# Main_Board.net
KiCad netlist of a schematic drawn in EAGLE
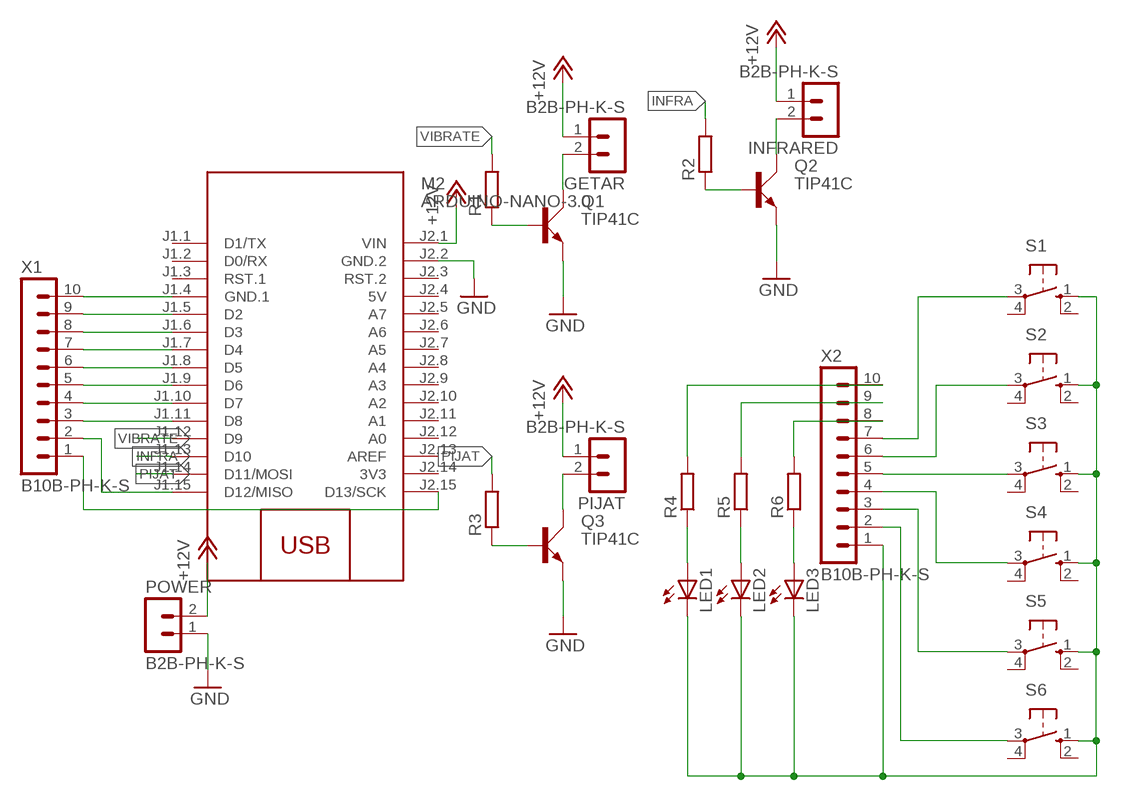
[diagram p0: schematic, sheet 1]

(export (version "E")
  (design (tool "Eeschema 10.0.6"))
  (components
    (comp (ref "GETAR")
      (value "B2B-PH-K-S")
      (footprint "eagle-import:B2B-PH-K-S")
      (libsource (lib "eagle-import") (part "B2B-PH-K-S"))
    )
    (comp (ref "INFRARED")
      (value "B2B-PH-K-S")
      (footprint "eagle-import:B2B-PH-K-S")
      (libsource (lib "eagle-import") (part "B2B-PH-K-S"))
    )
    (comp (ref "LED1")
      (value "LED5MM")
      (footprint "eagle-import:LED5MM")
      (libsource (lib "eagle-import") (part "LED5MM"))
    )
    (comp (ref "LED2")
      (value "LED5MM")
      (footprint "eagle-import:LED5MM")
      (libsource (lib "eagle-import") (part "LED5MM"))
    )
    (comp (ref "LED3")
      (value "LED5MM")
      (footprint "eagle-import:LED5MM")
      (libsource (lib "eagle-import") (part "LED5MM"))
    )
    (comp (ref "M2")
      (value "ARDUINO-NANO-3.0")
      (footprint "eagle-import:ARDUINO-NANO-3.0")
      (libsource (lib "eagle-import") (part "ARDUINO-NANO-3.0"))
    )
    (comp (ref "PIJAT")
      (value "B2B-PH-K-S")
      (footprint "eagle-import:B2B-PH-K-S")
      (libsource (lib "eagle-import") (part "B2B-PH-K-S"))
    )
    (comp (ref "POWER")
      (value "B2B-PH-K-S")
      (footprint "eagle-import:B2B-PH-K-S")
      (libsource (lib "eagle-import") (part "B2B-PH-K-S"))
    )
    (comp (ref "Q1")
      (value "TIP41C")
      (footprint "eagle-import:TO220AV")
      (libsource (lib "eagle-import") (part "TIP41C"))
    )
    (comp (ref "Q2")
      (value "TIP41C")
      (footprint "eagle-import:TO220AV")
      (libsource (lib "eagle-import") (part "TIP41C"))
    )
    (comp (ref "Q3")
      (value "TIP41C")
      (footprint "eagle-import:TO220AV")
      (libsource (lib "eagle-import") (part "TIP41C"))
    )
    (comp (ref "R1")
      (value "R-EU_0207/12")
      (footprint "eagle-import:0207_12")
      (libsource (lib "eagle-import") (part "R-EU_0207/12"))
    )
    (comp (ref "R2")
      (value "R-EU_0207/12")
      (footprint "eagle-import:0207_12")
      (libsource (lib "eagle-import") (part "R-EU_0207/12"))
    )
    (comp (ref "R3")
      (value "R-EU_0207/12")
      (footprint "eagle-import:0207_12")
      (libsource (lib "eagle-import") (part "R-EU_0207/12"))
    )
    (comp (ref "R4")
      (value "R-EU_0207/12")
      (footprint "eagle-import:0207_12")
      (libsource (lib "eagle-import") (part "R-EU_0207/12"))
    )
    (comp (ref "R5")
      (value "R-EU_0207/12")
      (footprint "eagle-import:0207_12")
      (libsource (lib "eagle-import") (part "R-EU_0207/12"))
    )
    (comp (ref "R6")
      (value "R-EU_0207/12")
      (footprint "eagle-import:0207_12")
      (libsource (lib "eagle-import") (part "R-EU_0207/12"))
    )
    (comp (ref "S1")
      (value "40-XX")
      (footprint "eagle-import:B3F-40XX")
      (fields (field (name "MF") "OMRON COMPONENTS USA") (field (name "MPN") "B3F-4000"))
      (libsource (lib "eagle-import") (part "40-XX"))
    )
    (comp (ref "S2")
      (value "40-XX")
      (footprint "eagle-import:B3F-40XX")
      (fields (field (name "MF") "OMRON COMPONENTS USA") (field (name "MPN") "B3F-4000"))
      (libsource (lib "eagle-import") (part "40-XX"))
    )
    (comp (ref "S3")
      (value "40-XX")
      (footprint "eagle-import:B3F-40XX")
      (fields (field (name "MF") "OMRON COMPONENTS USA") (field (name "MPN") "B3F-4000"))
      (libsource (lib "eagle-import") (part "40-XX"))
    )
    (comp (ref "S4")
      (value "40-XX")
      (footprint "eagle-import:B3F-40XX")
      (fields (field (name "MF") "OMRON COMPONENTS USA") (field (name "MPN") "B3F-4000"))
      (libsource (lib "eagle-import") (part "40-XX"))
    )
    (comp (ref "S5")
      (value "40-XX")
      (footprint "eagle-import:B3F-40XX")
      (fields (field (name "MF") "OMRON COMPONENTS USA") (field (name "MPN") "B3F-4000"))
      (libsource (lib "eagle-import") (part "40-XX"))
    )
    (comp (ref "S6")
      (value "40-XX")
      (footprint "eagle-import:B3F-40XX")
      (fields (field (name "MF") "OMRON COMPONENTS USA") (field (name "MPN") "B3F-4000"))
      (libsource (lib "eagle-import") (part "40-XX"))
    )
    (comp (ref "X1")
      (value "B10B-PH-K-S")
      (footprint "eagle-import:B10B-PH-K-S")
      (libsource (lib "eagle-import") (part "B10B-PH-K-S"))
    )
    (comp (ref "X2")
      (value "B10B-PH-K-S")
      (footprint "eagle-import:B10B-PH-K-S")
      (libsource (lib "eagle-import") (part "B10B-PH-K-S"))
    )
  )
  (nets
    (net (code "1") (name "+12V") (class "Default")
      (node (ref "GETAR") (pin "1") (pinfunction "1_1") (pintype "passive"))
      (node (ref "INFRARED") (pin "1") (pinfunction "1_1") (pintype "passive"))
      (node (ref "M2") (pin "J2.1") (pinfunction "VIN_J2.1") (pintype "power_in"))
      (node (ref "PIJAT") (pin "1") (pinfunction "1_1") (pintype "passive"))
      (node (ref "POWER") (pin "2") (pinfunction "2_2") (pintype "passive"))
    )
    (net (code "2") (name "/3V3") (class "Default")
      (node (ref "M2") (pin "J2.14") (pinfunction "3V3_J2.14") (pintype "power_in"))
    )
    (net (code "3") (name "/5V") (class "Default")
      (node (ref "M2") (pin "J2.4") (pinfunction "5V_J2.4") (pintype "power_in"))
    )
    (net (code "4") (name "GND") (class "Default")
      (node (ref "M2") (pin "J2.2") (pinfunction "GND.2_J2.2") (pintype "power_in"))
      (node (ref "POWER") (pin "1") (pinfunction "1_1") (pintype "passive"))
      (node (ref "Q1") (pin "E") (pinfunction "E_E") (pintype "passive"))
      (node (ref "Q2") (pin "E") (pinfunction "E_E") (pintype "passive"))
      (node (ref "Q3") (pin "E") (pinfunction "E_E") (pintype "passive"))
    )
    (net (code "5") (name "INFRA") (class "Default")
      (node (ref "M2") (pin "J1.13") (pinfunction "D10_J1.13") (pintype "bidirectional"))
      (node (ref "R2") (pin "2") (pinfunction "2_2") (pintype "passive"))
    )
    (net (code "6") (name "Net-(GETAR-Pad2)") (class "Default")
      (node (ref "GETAR") (pin "2") (pinfunction "2_2") (pintype "passive"))
      (node (ref "Q1") (pin "C") (pinfunction "C_C") (pintype "passive"))
    )
    (net (code "7") (name "Net-(INFRARED-Pad2)") (class "Default")
      (node (ref "INFRARED") (pin "2") (pinfunction "2_2") (pintype "passive"))
      (node (ref "Q2") (pin "C") (pinfunction "C_C") (pintype "passive"))
    )
    (net (code "8") (name "Net-(LED1-C)") (class "Default")
      (node (ref "LED1") (pin "K") (pinfunction "C_K") (pintype "passive"))
      (node (ref "LED2") (pin "K") (pinfunction "C_K") (pintype "passive"))
      (node (ref "LED3") (pin "K") (pinfunction "C_K") (pintype "passive"))
      (node (ref "S1") (pin "1") (pinfunction "S_1") (pintype "passive"))
      (node (ref "S2") (pin "1") (pinfunction "S_1") (pintype "passive"))
      (node (ref "S3") (pin "1") (pinfunction "S_1") (pintype "passive"))
      (node (ref "S4") (pin "1") (pinfunction "S_1") (pintype "passive"))
      (node (ref "S5") (pin "1") (pinfunction "S_1") (pintype "passive"))
      (node (ref "S6") (pin "1") (pinfunction "S_1") (pintype "passive"))
      (node (ref "X2") (pin "1") (pinfunction "1_1") (pintype "passive"))
    )
    (net (code "9") (name "Net-(LED1-PadA)") (class "Default")
      (node (ref "LED1") (pin "A") (pinfunction "A_A") (pintype "passive"))
      (node (ref "R4") (pin "1") (pinfunction "1_1") (pintype "passive"))
    )
    (net (code "10") (name "Net-(LED2-PadA)") (class "Default")
      (node (ref "LED2") (pin "A") (pinfunction "A_A") (pintype "passive"))
      (node (ref "R5") (pin "1") (pinfunction "1_1") (pintype "passive"))
    )
    (net (code "11") (name "Net-(LED3-PadA)") (class "Default")
      (node (ref "LED3") (pin "A") (pinfunction "A_A") (pintype "passive"))
      (node (ref "R6") (pin "1") (pinfunction "1_1") (pintype "passive"))
    )
    (net (code "12") (name "Net-(M2-D2)") (class "Default")
      (node (ref "M2") (pin "J1.5") (pinfunction "D2_J1.5") (pintype "bidirectional"))
      (node (ref "X1") (pin "9") (pinfunction "9_9") (pintype "passive"))
    )
    (net (code "13") (name "Net-(M2-D3)") (class "Default")
      (node (ref "M2") (pin "J1.6") (pinfunction "D3_J1.6") (pintype "bidirectional"))
      (node (ref "X1") (pin "8") (pinfunction "8_8") (pintype "passive"))
    )
    (net (code "14") (name "Net-(M2-D4)") (class "Default")
      (node (ref "M2") (pin "J1.7") (pinfunction "D4_J1.7") (pintype "bidirectional"))
      (node (ref "X1") (pin "7") (pinfunction "7_7") (pintype "passive"))
    )
    (net (code "15") (name "Net-(M2-D5)") (class "Default")
      (node (ref "M2") (pin "J1.8") (pinfunction "D5_J1.8") (pintype "bidirectional"))
      (node (ref "X1") (pin "6") (pinfunction "6_6") (pintype "passive"))
    )
    (net (code "16") (name "Net-(M2-D6)") (class "Default")
      (node (ref "M2") (pin "J1.9") (pinfunction "D6_J1.9") (pintype "bidirectional"))
      (node (ref "X1") (pin "5") (pinfunction "5_5") (pintype "passive"))
    )
    (net (code "17") (name "Net-(M2-D7)") (class "Default")
      (node (ref "M2") (pin "J1.10") (pinfunction "D7_J1.10") (pintype "bidirectional"))
      (node (ref "X1") (pin "4") (pinfunction "4_4") (pintype "passive"))
    )
    (net (code "18") (name "Net-(M2-D8)") (class "Default")
      (node (ref "M2") (pin "J1.11") (pinfunction "D8_J1.11") (pintype "bidirectional"))
      (node (ref "X1") (pin "3") (pinfunction "3_3") (pintype "passive"))
    )
    (net (code "19") (name "Net-(M2-D12{slash}MISO)") (class "Default")
      (node (ref "M2") (pin "J1.15") (pinfunction "D12/MISO_J1.15") (pintype "bidirectional"))
      (node (ref "X1") (pin "2") (pinfunction "2_2") (pintype "passive"))
    )
    (net (code "20") (name "Net-(M2-D13{slash}SCK)") (class "Default")
      (node (ref "M2") (pin "J2.15") (pinfunction "D13/SCK_J2.15") (pintype "bidirectional"))
      (node (ref "X1") (pin "1") (pinfunction "1_1") (pintype "passive"))
    )
    (net (code "21") (name "Net-(M2-GND.1)") (class "Default")
      (node (ref "M2") (pin "J1.4") (pinfunction "GND.1_J1.4") (pintype "power_in"))
      (node (ref "X1") (pin "10") (pinfunction "10_10") (pintype "passive"))
    )
    (net (code "22") (name "Net-(PIJAT-Pad2)") (class "Default")
      (node (ref "PIJAT") (pin "2") (pinfunction "2_2") (pintype "passive"))
      (node (ref "Q3") (pin "C") (pinfunction "C_C") (pintype "passive"))
    )
    (net (code "23") (name "Net-(Q1-PadB)") (class "Default")
      (node (ref "Q1") (pin "B") (pinfunction "B_B") (pintype "passive"))
      (node (ref "R1") (pin "1") (pinfunction "1_1") (pintype "passive"))
    )
    (net (code "24") (name "Net-(Q2-PadB)") (class "Default")
      (node (ref "Q2") (pin "B") (pinfunction "B_B") (pintype "passive"))
      (node (ref "R2") (pin "1") (pinfunction "1_1") (pintype "passive"))
    )
    (net (code "25") (name "Net-(Q3-PadB)") (class "Default")
      (node (ref "Q3") (pin "B") (pinfunction "B_B") (pintype "passive"))
      (node (ref "R3") (pin "1") (pinfunction "1_1") (pintype "passive"))
    )
    (net (code "26") (name "Net-(R4-Pad2)") (class "Default")
      (node (ref "R4") (pin "2") (pinfunction "2_2") (pintype "passive"))
      (node (ref "X2") (pin "10") (pinfunction "10_10") (pintype "passive"))
    )
    (net (code "27") (name "Net-(R5-Pad2)") (class "Default")
      (node (ref "R5") (pin "2") (pinfunction "2_2") (pintype "passive"))
      (node (ref "X2") (pin "9") (pinfunction "9_9") (pintype "passive"))
    )
    (net (code "28") (name "Net-(R6-Pad2)") (class "Default")
      (node (ref "R6") (pin "2") (pinfunction "2_2") (pintype "passive"))
      (node (ref "X2") (pin "8") (pinfunction "8_8") (pintype "passive"))
    )
    (net (code "29") (name "Net-(S1-P)") (class "Default")
      (node (ref "S1") (pin "3") (pinfunction "P_3") (pintype "passive"))
      (node (ref "X2") (pin "7") (pinfunction "7_7") (pintype "passive"))
    )
    (net (code "30") (name "Net-(S2-P)") (class "Default")
      (node (ref "S2") (pin "3") (pinfunction "P_3") (pintype "passive"))
      (node (ref "X2") (pin "6") (pinfunction "6_6") (pintype "passive"))
    )
    (net (code "31") (name "Net-(S3-P)") (class "Default")
      (node (ref "S3") (pin "3") (pinfunction "P_3") (pintype "passive"))
      (node (ref "X2") (pin "5") (pinfunction "5_5") (pintype "passive"))
    )
    (net (code "32") (name "Net-(S4-P)") (class "Default")
      (node (ref "S4") (pin "3") (pinfunction "P_3") (pintype "passive"))
      (node (ref "X2") (pin "4") (pinfunction "4_4") (pintype "passive"))
    )
    (net (code "33") (name "Net-(S5-P)") (class "Default")
      (node (ref "S5") (pin "3") (pinfunction "P_3") (pintype "passive"))
      (node (ref "X2") (pin "3") (pinfunction "3_3") (pintype "passive"))
    )
    (net (code "34") (name "Net-(S6-P)") (class "Default")
      (node (ref "S6") (pin "3") (pinfunction "P_3") (pintype "passive"))
      (node (ref "X2") (pin "2") (pinfunction "2_2") (pintype "passive"))
    )
    (net (code "35") (name "PIJAT") (class "Default")
      (node (ref "M2") (pin "J1.14") (pinfunction "D11/MOSI_J1.14") (pintype "bidirectional"))
      (node (ref "R3") (pin "2") (pinfunction "2_2") (pintype "passive"))
    )
    (net (code "36") (name "VIBRATE") (class "Default")
      (node (ref "M2") (pin "J1.12") (pinfunction "D9_J1.12") (pintype "bidirectional"))
      (node (ref "R1") (pin "2") (pinfunction "2_2") (pintype "passive"))
    )
    (net (code "37") (name "unconnected-(M2-A0-PadJ2.12)") (class "Default")
      (node (ref "M2") (pin "J2.12") (pinfunction "A0_J2.12") (pintype "bidirectional"))
    )
    (net (code "38") (name "unconnected-(M2-A1-PadJ2.11)") (class "Default")
      (node (ref "M2") (pin "J2.11") (pinfunction "A1_J2.11") (pintype "bidirectional"))
    )
    (net (code "39") (name "unconnected-(M2-A2-PadJ2.10)") (class "Default")
      (node (ref "M2") (pin "J2.10") (pinfunction "A2_J2.10") (pintype "bidirectional"))
    )
    (net (code "40") (name "unconnected-(M2-A3-PadJ2.9)") (class "Default")
      (node (ref "M2") (pin "J2.9") (pinfunction "A3_J2.9") (pintype "bidirectional"))
    )
    (net (code "41") (name "unconnected-(M2-A4-PadJ2.8)") (class "Default")
      (node (ref "M2") (pin "J2.8") (pinfunction "A4_J2.8") (pintype "bidirectional"))
    )
    (net (code "42") (name "unconnected-(M2-A5-PadJ2.7)") (class "Default")
      (node (ref "M2") (pin "J2.7") (pinfunction "A5_J2.7") (pintype "bidirectional"))
    )
    (net (code "43") (name "unconnected-(M2-A6-PadJ2.6)") (class "Default")
      (node (ref "M2") (pin "J2.6") (pinfunction "A6_J2.6") (pintype "bidirectional"))
    )
    (net (code "44") (name "unconnected-(M2-A7-PadJ2.5)") (class "Default")
      (node (ref "M2") (pin "J2.5") (pinfunction "A7_J2.5") (pintype "bidirectional"))
    )
    (net (code "45") (name "unconnected-(M2-AREF-PadJ2.13)") (class "Default")
      (node (ref "M2") (pin "J2.13") (pinfunction "AREF_J2.13") (pintype "bidirectional"))
    )
    (net (code "46") (name "unconnected-(M2-D0{slash}RX-PadJ1.2)") (class "Default")
      (node (ref "M2") (pin "J1.2") (pinfunction "D0/RX_J1.2") (pintype "bidirectional"))
    )
    (net (code "47") (name "unconnected-(M2-D1{slash}TX-PadJ1.1)") (class "Default")
      (node (ref "M2") (pin "J1.1") (pinfunction "D1/TX_J1.1") (pintype "bidirectional"))
    )
    (net (code "48") (name "unconnected-(M2-RST.1-PadJ1.3)") (class "Default")
      (node (ref "M2") (pin "J1.3") (pinfunction "RST.1_J1.3") (pintype "bidirectional"))
    )
    (net (code "49") (name "unconnected-(M2-RST.2-PadJ2.3)") (class "Default")
      (node (ref "M2") (pin "J2.3") (pinfunction "RST.2_J2.3") (pintype "bidirectional"))
    )
    (net (code "50") (name "unconnected-(S1-P1-Pad4)") (class "Default")
      (node (ref "S1") (pin "4") (pinfunction "P1_4") (pintype "passive"))
    )
    (net (code "51") (name "unconnected-(S1-S1-Pad2)") (class "Default")
      (node (ref "S1") (pin "2") (pinfunction "S1_2") (pintype "passive"))
    )
    (net (code "52") (name "unconnected-(S2-P1-Pad4)") (class "Default")
      (node (ref "S2") (pin "4") (pinfunction "P1_4") (pintype "passive"))
    )
    (net (code "53") (name "unconnected-(S2-S1-Pad2)") (class "Default")
      (node (ref "S2") (pin "2") (pinfunction "S1_2") (pintype "passive"))
    )
    (net (code "54") (name "unconnected-(S3-P1-Pad4)") (class "Default")
      (node (ref "S3") (pin "4") (pinfunction "P1_4") (pintype "passive"))
    )
    (net (code "55") (name "unconnected-(S3-S1-Pad2)") (class "Default")
      (node (ref "S3") (pin "2") (pinfunction "S1_2") (pintype "passive"))
    )
    (net (code "56") (name "unconnected-(S4-P1-Pad4)") (class "Default")
      (node (ref "S4") (pin "4") (pinfunction "P1_4") (pintype "passive"))
    )
    (net (code "57") (name "unconnected-(S4-S1-Pad2)") (class "Default")
      (node (ref "S4") (pin "2") (pinfunction "S1_2") (pintype "passive"))
    )
    (net (code "58") (name "unconnected-(S5-P1-Pad4)") (class "Default")
      (node (ref "S5") (pin "4") (pinfunction "P1_4") (pintype "passive"))
    )
    (net (code "59") (name "unconnected-(S5-S1-Pad2)") (class "Default")
      (node (ref "S5") (pin "2") (pinfunction "S1_2") (pintype "passive"))
    )
    (net (code "60") (name "unconnected-(S6-P1-Pad4)") (class "Default")
      (node (ref "S6") (pin "4") (pinfunction "P1_4") (pintype "passive"))
    )
    (net (code "61") (name "unconnected-(S6-S1-Pad2)") (class "Default")
      (node (ref "S6") (pin "2") (pinfunction "S1_2") (pintype "passive"))
    )
  )
)
